# main.net
KiCad netlist of a schematic drawn in Altium Designer
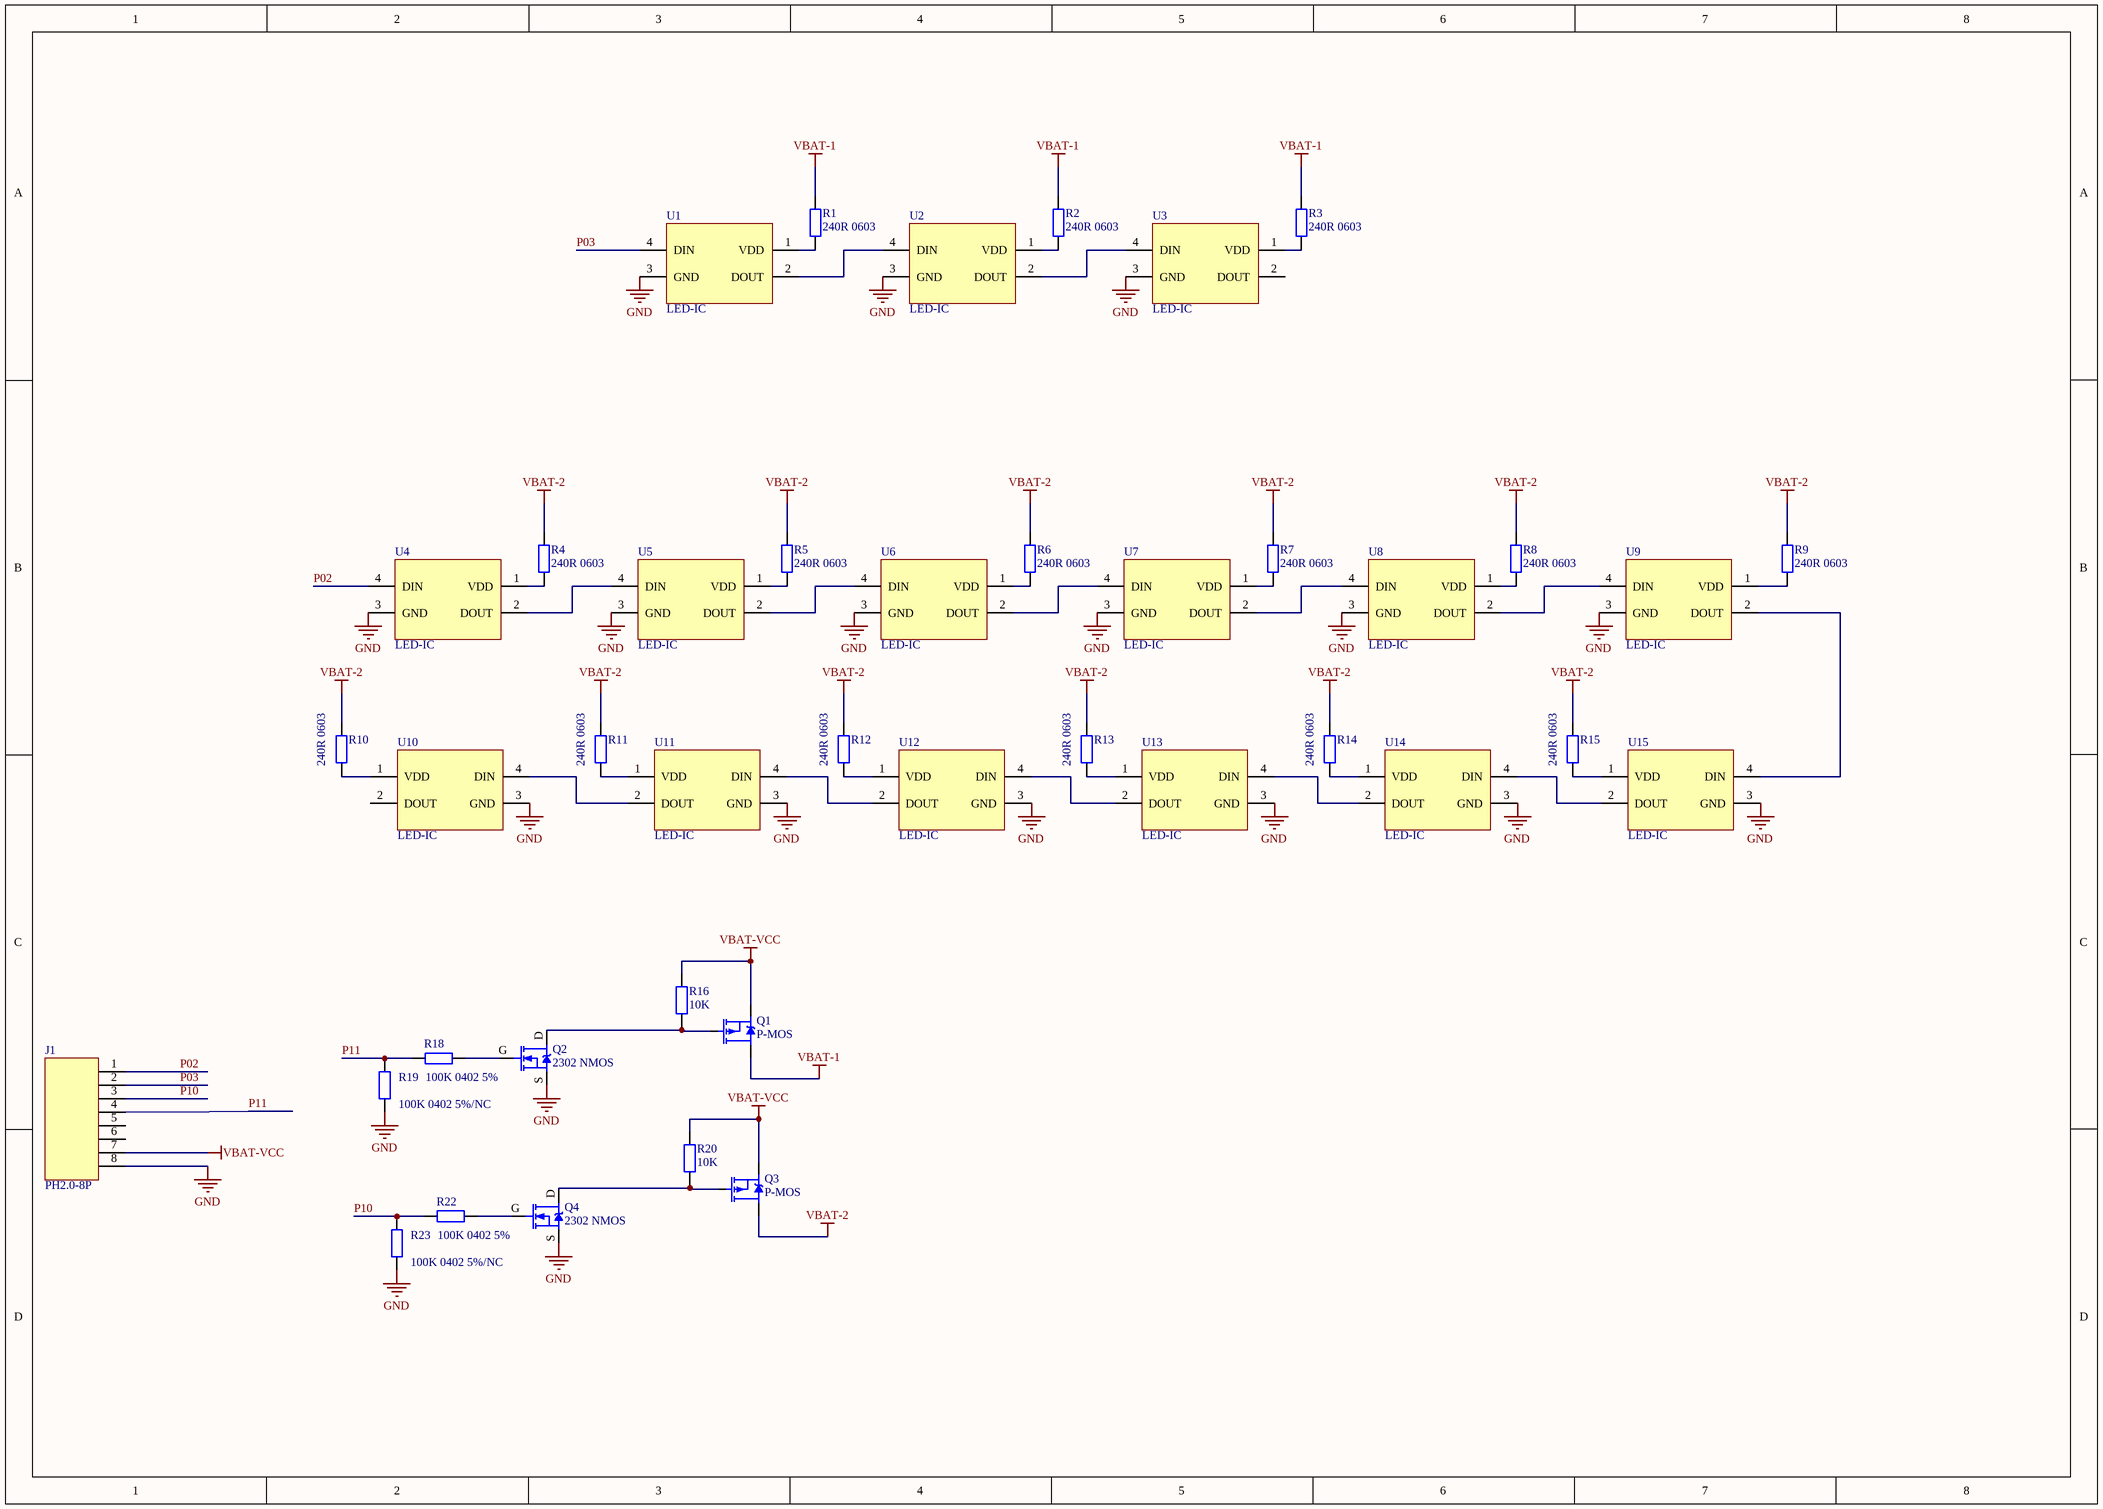
[diagram p0: main.SchDoc]

(export (version "E")
  (design (tool "Eeschema 10.0.6"))
  (components
    (comp (ref "J1") (value "PH2.0-8P") (footprint "PH2.0-8P") (libsource (lib "PH") (part "PH2.0-8P")))
    (comp (ref "Q1")
      (value "P-MOS")
      (footprint "SOT23")
      (description "P沟道场效应管")
      (libsource (lib "MOS管") (part "P-MOS"))
    )
    (comp (ref "Q2")
      (value "2302 NMOS")
      (footprint "SOT23")
      (description "N沟道场效应管")
      (libsource (lib "MOS管") (part "N-MOS"))
    )
    (comp (ref "Q3")
      (value "P-MOS")
      (footprint "SOT23")
      (description "P沟道场效应管")
      (libsource (lib "MOS管") (part "P-MOS"))
    )
    (comp (ref "Q4")
      (value "2302 NMOS")
      (footprint "SOT23")
      (description "N沟道场效应管")
      (libsource (lib "MOS管") (part "N-MOS"))
    )
    (comp (ref "R1")
      (value "240R 0603")
      (footprint "R 0603")
      (description "贴片电阻")
      (fields (field (name "版权归属") "源创客"))
      (libsource (lib "源创客") (part "R"))
    )
    (comp (ref "R2")
      (value "240R 0603")
      (footprint "R 0603")
      (description "贴片电阻")
      (fields (field (name "版权归属") "源创客"))
      (libsource (lib "源创客") (part "R"))
    )
    (comp (ref "R3")
      (value "240R 0603")
      (footprint "R 0603")
      (description "贴片电阻")
      (fields (field (name "版权归属") "源创客"))
      (libsource (lib "源创客") (part "R"))
    )
    (comp (ref "R4")
      (value "240R 0603")
      (footprint "R 0603")
      (description "贴片电阻")
      (fields (field (name "版权归属") "源创客"))
      (libsource (lib "源创客") (part "R"))
    )
    (comp (ref "R5")
      (value "240R 0603")
      (footprint "R 0603")
      (description "贴片电阻")
      (fields (field (name "版权归属") "源创客"))
      (libsource (lib "源创客") (part "R"))
    )
    (comp (ref "R6")
      (value "240R 0603")
      (footprint "R 0603")
      (description "贴片电阻")
      (fields (field (name "版权归属") "源创客"))
      (libsource (lib "源创客") (part "R"))
    )
    (comp (ref "R7")
      (value "240R 0603")
      (footprint "R 0603")
      (description "贴片电阻")
      (fields (field (name "版权归属") "源创客"))
      (libsource (lib "源创客") (part "R"))
    )
    (comp (ref "R8")
      (value "240R 0603")
      (footprint "R 0603")
      (description "贴片电阻")
      (fields (field (name "版权归属") "源创客"))
      (libsource (lib "源创客") (part "R"))
    )
    (comp (ref "R9")
      (value "240R 0603")
      (footprint "R 0603")
      (description "贴片电阻")
      (fields (field (name "版权归属") "源创客"))
      (libsource (lib "源创客") (part "R"))
    )
    (comp (ref "R10")
      (value "240R 0603")
      (footprint "R 0603")
      (description "贴片电阻")
      (fields (field (name "版权归属") "源创客"))
      (libsource (lib "源创客") (part "R"))
    )
    (comp (ref "R11")
      (value "240R 0603")
      (footprint "R 0603")
      (description "贴片电阻")
      (fields (field (name "版权归属") "源创客"))
      (libsource (lib "源创客") (part "R"))
    )
    (comp (ref "R12")
      (value "240R 0603")
      (footprint "R 0603")
      (description "贴片电阻")
      (fields (field (name "版权归属") "源创客"))
      (libsource (lib "源创客") (part "R"))
    )
    (comp (ref "R13")
      (value "240R 0603")
      (footprint "R 0603")
      (description "贴片电阻")
      (fields (field (name "版权归属") "源创客"))
      (libsource (lib "源创客") (part "R"))
    )
    (comp (ref "R14")
      (value "240R 0603")
      (footprint "R 0603")
      (description "贴片电阻")
      (fields (field (name "版权归属") "源创客"))
      (libsource (lib "源创客") (part "R"))
    )
    (comp (ref "R15")
      (value "240R 0603")
      (footprint "R 0603")
      (description "贴片电阻")
      (fields (field (name "版权归属") "源创客"))
      (libsource (lib "源创客") (part "R"))
    )
    (comp (ref "R16")
      (value "10K")
      (footprint "R 0603")
      (description "贴片电阻")
      (fields (field (name "版权归属") "源创客"))
      (libsource (lib "源创客") (part "R"))
    )
    (comp (ref "R18")
      (value "100K 0402 5%")
      (footprint "R 0603")
      (description "贴片电阻")
      (fields (field (name "版权归属") "源创客"))
      (libsource (lib "源创客") (part "R"))
    )
    (comp (ref "R19")
      (value "100K 0402 5%/NC")
      (footprint "R 0603")
      (description "贴片电阻")
      (fields (field (name "版权归属") "源创客"))
      (libsource (lib "源创客") (part "R"))
    )
    (comp (ref "R20")
      (value "10K")
      (footprint "R 0603")
      (description "贴片电阻")
      (fields (field (name "版权归属") "源创客"))
      (libsource (lib "源创客") (part "R"))
    )
    (comp (ref "R22")
      (value "100K 0402 5%")
      (footprint "R 0603")
      (description "贴片电阻")
      (fields (field (name "版权归属") "源创客"))
      (libsource (lib "源创客") (part "R"))
    )
    (comp (ref "R23")
      (value "100K 0402 5%/NC")
      (footprint "R 0603")
      (description "贴片电阻")
      (fields (field (name "版权归属") "源创客"))
      (libsource (lib "源创客") (part "R"))
    )
    (comp (ref "U1")
      (value "LED-IC")
      (footprint "LED-SMD_4P-L5.0-W5.0-BL_TC5050RGB")
      (libsource (lib "") (part "TC5050RGB_1"))
    )
    (comp (ref "U2")
      (value "LED-IC")
      (footprint "LED-SMD_4P-L5.0-W5.0-BL_TC5050RGB")
      (libsource (lib "") (part "TC5050RGB_1"))
    )
    (comp (ref "U3")
      (value "LED-IC")
      (footprint "LED-SMD_4P-L5.0-W5.0-BL_TC5050RGB")
      (libsource (lib "") (part "TC5050RGB_1"))
    )
    (comp (ref "U4")
      (value "LED-IC")
      (footprint "LED-SMD_4P-L5.0-W5.0-BL_TC5050RGB")
      (libsource (lib "") (part "TC5050RGB_1"))
    )
    (comp (ref "U5")
      (value "LED-IC")
      (footprint "LED-SMD_4P-L5.0-W5.0-BL_TC5050RGB")
      (libsource (lib "") (part "TC5050RGB_1"))
    )
    (comp (ref "U6")
      (value "LED-IC")
      (footprint "LED-SMD_4P-L5.0-W5.0-BL_TC5050RGB")
      (libsource (lib "") (part "TC5050RGB_1"))
    )
    (comp (ref "U7")
      (value "LED-IC")
      (footprint "LED-SMD_4P-L5.0-W5.0-BL_TC5050RGB")
      (libsource (lib "") (part "TC5050RGB_1"))
    )
    (comp (ref "U8")
      (value "LED-IC")
      (footprint "LED-SMD_4P-L5.0-W5.0-BL_TC5050RGB")
      (libsource (lib "") (part "TC5050RGB_1"))
    )
    (comp (ref "U9")
      (value "LED-IC")
      (footprint "LED-SMD_4P-L5.0-W5.0-BL_TC5050RGB")
      (libsource (lib "") (part "TC5050RGB_1"))
    )
    (comp (ref "U10")
      (value "LED-IC")
      (footprint "LED-SMD_4P-L5.0-W5.0-BL_TC5050RGB")
      (libsource (lib "Schlib1") (part "TC5050RGB"))
    )
    (comp (ref "U11")
      (value "LED-IC")
      (footprint "LED-SMD_4P-L5.0-W5.0-BL_TC5050RGB")
      (libsource (lib "Schlib1") (part "TC5050RGB"))
    )
    (comp (ref "U12")
      (value "LED-IC")
      (footprint "LED-SMD_4P-L5.0-W5.0-BL_TC5050RGB")
      (libsource (lib "Schlib1") (part "TC5050RGB"))
    )
    (comp (ref "U13")
      (value "LED-IC")
      (footprint "LED-SMD_4P-L5.0-W5.0-BL_TC5050RGB")
      (libsource (lib "Schlib1") (part "TC5050RGB"))
    )
    (comp (ref "U14")
      (value "LED-IC")
      (footprint "LED-SMD_4P-L5.0-W5.0-BL_TC5050RGB")
      (libsource (lib "Schlib1") (part "TC5050RGB"))
    )
    (comp (ref "U15")
      (value "LED-IC")
      (footprint "LED-SMD_4P-L5.0-W5.0-BL_TC5050RGB")
      (libsource (lib "Schlib1") (part "TC5050RGB"))
    )
  )
  (nets
    (net (code "1") (name "/P02") (class "Default")
      (node (ref "J1") (pin "1") (pinfunction "1_1") (pintype "passive"))
      (node (ref "U4") (pin "4") (pinfunction "DIN_4") (pintype "passive"))
    )
    (net (code "2") (name "/P03") (class "Default")
      (node (ref "J1") (pin "2") (pinfunction "2_2") (pintype "passive"))
      (node (ref "U1") (pin "4") (pinfunction "DIN_4") (pintype "passive"))
    )
    (net (code "3") (name "/P10") (class "Default")
      (node (ref "J1") (pin "3") (pinfunction "3_3") (pintype "passive"))
      (node (ref "R22") (pin "1") (pinfunction "1_1") (pintype "passive"))
      (node (ref "R23") (pin "2") (pinfunction "2_2") (pintype "passive"))
    )
    (net (code "4") (name "/P11") (class "Default")
      (node (ref "J1") (pin "4") (pinfunction "4_4") (pintype "passive"))
      (node (ref "R18") (pin "1") (pinfunction "1_1") (pintype "passive"))
      (node (ref "R19") (pin "2") (pinfunction "2_2") (pintype "passive"))
    )
    (net (code "5") (name "GND") (class "Default")
      (node (ref "J1") (pin "8") (pinfunction "8_8") (pintype "passive"))
      (node (ref "Q2") (pin "S") (pinfunction "S_S") (pintype "passive"))
      (node (ref "Q4") (pin "S") (pinfunction "S_S") (pintype "passive"))
      (node (ref "R19") (pin "1") (pinfunction "1_1") (pintype "passive"))
      (node (ref "R23") (pin "1") (pinfunction "1_1") (pintype "passive"))
      (node (ref "U1") (pin "3") (pinfunction "GND_3") (pintype "passive"))
      (node (ref "U10") (pin "3") (pinfunction "GND_3") (pintype "passive"))
      (node (ref "U11") (pin "3") (pinfunction "GND_3") (pintype "passive"))
      (node (ref "U12") (pin "3") (pinfunction "GND_3") (pintype "passive"))
      (node (ref "U13") (pin "3") (pinfunction "GND_3") (pintype "passive"))
      (node (ref "U14") (pin "3") (pinfunction "GND_3") (pintype "passive"))
      (node (ref "U15") (pin "3") (pinfunction "GND_3") (pintype "passive"))
      (node (ref "U2") (pin "3") (pinfunction "GND_3") (pintype "passive"))
      (node (ref "U3") (pin "3") (pinfunction "GND_3") (pintype "passive"))
      (node (ref "U4") (pin "3") (pinfunction "GND_3") (pintype "passive"))
      (node (ref "U5") (pin "3") (pinfunction "GND_3") (pintype "passive"))
      (node (ref "U6") (pin "3") (pinfunction "GND_3") (pintype "passive"))
      (node (ref "U7") (pin "3") (pinfunction "GND_3") (pintype "passive"))
      (node (ref "U8") (pin "3") (pinfunction "GND_3") (pintype "passive"))
      (node (ref "U9") (pin "3") (pinfunction "GND_3") (pintype "passive"))
    )
    (net (code "6") (name "Net-(Q1-PadG)") (class "Default")
      (node (ref "Q1") (pin "G") (pinfunction "G_G") (pintype "passive"))
      (node (ref "Q2") (pin "D") (pinfunction "D_D") (pintype "passive"))
      (node (ref "R16") (pin "1") (pinfunction "1_1") (pintype "passive"))
    )
    (net (code "7") (name "Net-(Q2-PadG)") (class "Default")
      (node (ref "Q2") (pin "G") (pinfunction "G_G") (pintype "passive"))
      (node (ref "R18") (pin "2") (pinfunction "2_2") (pintype "passive"))
    )
    (net (code "8") (name "Net-(Q3-PadG)") (class "Default")
      (node (ref "Q3") (pin "G") (pinfunction "G_G") (pintype "passive"))
      (node (ref "Q4") (pin "D") (pinfunction "D_D") (pintype "passive"))
      (node (ref "R20") (pin "1") (pinfunction "1_1") (pintype "passive"))
    )
    (net (code "9") (name "Net-(Q4-PadG)") (class "Default")
      (node (ref "Q4") (pin "G") (pinfunction "G_G") (pintype "passive"))
      (node (ref "R22") (pin "2") (pinfunction "2_2") (pintype "passive"))
    )
    (net (code "10") (name "Net-(U1-DOUT)") (class "Default")
      (node (ref "U1") (pin "2") (pinfunction "DOUT_2") (pintype "passive"))
      (node (ref "U2") (pin "4") (pinfunction "DIN_4") (pintype "passive"))
    )
    (net (code "11") (name "Net-(U1-VDD)") (class "Default")
      (node (ref "R1") (pin "1") (pinfunction "1_1") (pintype "passive"))
      (node (ref "U1") (pin "1") (pinfunction "VDD_1") (pintype "passive"))
    )
    (net (code "12") (name "Net-(U2-DOUT)") (class "Default")
      (node (ref "U2") (pin "2") (pinfunction "DOUT_2") (pintype "passive"))
      (node (ref "U3") (pin "4") (pinfunction "DIN_4") (pintype "passive"))
    )
    (net (code "13") (name "Net-(U2-VDD)") (class "Default")
      (node (ref "R2") (pin "1") (pinfunction "1_1") (pintype "passive"))
      (node (ref "U2") (pin "1") (pinfunction "VDD_1") (pintype "passive"))
    )
    (net (code "14") (name "Net-(U3-VDD)") (class "Default")
      (node (ref "R3") (pin "1") (pinfunction "1_1") (pintype "passive"))
      (node (ref "U3") (pin "1") (pinfunction "VDD_1") (pintype "passive"))
    )
    (net (code "15") (name "Net-(U4-DOUT)") (class "Default")
      (node (ref "U4") (pin "2") (pinfunction "DOUT_2") (pintype "passive"))
      (node (ref "U5") (pin "4") (pinfunction "DIN_4") (pintype "passive"))
    )
    (net (code "16") (name "Net-(U4-VDD)") (class "Default")
      (node (ref "R4") (pin "1") (pinfunction "1_1") (pintype "passive"))
      (node (ref "U4") (pin "1") (pinfunction "VDD_1") (pintype "passive"))
    )
    (net (code "17") (name "Net-(U5-DOUT)") (class "Default")
      (node (ref "U5") (pin "2") (pinfunction "DOUT_2") (pintype "passive"))
      (node (ref "U6") (pin "4") (pinfunction "DIN_4") (pintype "passive"))
    )
    (net (code "18") (name "Net-(U5-VDD)") (class "Default")
      (node (ref "R5") (pin "1") (pinfunction "1_1") (pintype "passive"))
      (node (ref "U5") (pin "1") (pinfunction "VDD_1") (pintype "passive"))
    )
    (net (code "19") (name "Net-(U6-DOUT)") (class "Default")
      (node (ref "U6") (pin "2") (pinfunction "DOUT_2") (pintype "passive"))
      (node (ref "U7") (pin "4") (pinfunction "DIN_4") (pintype "passive"))
    )
    (net (code "20") (name "Net-(U6-VDD)") (class "Default")
      (node (ref "R6") (pin "1") (pinfunction "1_1") (pintype "passive"))
      (node (ref "U6") (pin "1") (pinfunction "VDD_1") (pintype "passive"))
    )
    (net (code "21") (name "Net-(U7-DOUT)") (class "Default")
      (node (ref "U7") (pin "2") (pinfunction "DOUT_2") (pintype "passive"))
      (node (ref "U8") (pin "4") (pinfunction "DIN_4") (pintype "passive"))
    )
    (net (code "22") (name "Net-(U7-VDD)") (class "Default")
      (node (ref "R7") (pin "1") (pinfunction "1_1") (pintype "passive"))
      (node (ref "U7") (pin "1") (pinfunction "VDD_1") (pintype "passive"))
    )
    (net (code "23") (name "Net-(U8-DOUT)") (class "Default")
      (node (ref "U8") (pin "2") (pinfunction "DOUT_2") (pintype "passive"))
      (node (ref "U9") (pin "4") (pinfunction "DIN_4") (pintype "passive"))
    )
    (net (code "24") (name "Net-(U8-VDD)") (class "Default")
      (node (ref "R8") (pin "1") (pinfunction "1_1") (pintype "passive"))
      (node (ref "U8") (pin "1") (pinfunction "VDD_1") (pintype "passive"))
    )
    (net (code "25") (name "Net-(U9-VDD)") (class "Default")
      (node (ref "R9") (pin "1") (pinfunction "1_1") (pintype "passive"))
      (node (ref "U9") (pin "1") (pinfunction "VDD_1") (pintype "passive"))
    )
    (net (code "26") (name "Net-(U10-DIN)") (class "Default")
      (node (ref "U10") (pin "4") (pinfunction "DIN_4") (pintype "passive"))
      (node (ref "U11") (pin "2") (pinfunction "DOUT_2") (pintype "passive"))
    )
    (net (code "27") (name "Net-(U10-VDD)") (class "Default")
      (node (ref "R10") (pin "1") (pinfunction "1_1") (pintype "passive"))
      (node (ref "U10") (pin "1") (pinfunction "VDD_1") (pintype "passive"))
    )
    (net (code "28") (name "Net-(U11-DIN)") (class "Default")
      (node (ref "U11") (pin "4") (pinfunction "DIN_4") (pintype "passive"))
      (node (ref "U12") (pin "2") (pinfunction "DOUT_2") (pintype "passive"))
    )
    (net (code "29") (name "Net-(U11-VDD)") (class "Default")
      (node (ref "R11") (pin "1") (pinfunction "1_1") (pintype "passive"))
      (node (ref "U11") (pin "1") (pinfunction "VDD_1") (pintype "passive"))
    )
    (net (code "30") (name "Net-(U12-DIN)") (class "Default")
      (node (ref "U12") (pin "4") (pinfunction "DIN_4") (pintype "passive"))
      (node (ref "U13") (pin "2") (pinfunction "DOUT_2") (pintype "passive"))
    )
    (net (code "31") (name "Net-(U12-VDD)") (class "Default")
      (node (ref "R12") (pin "1") (pinfunction "1_1") (pintype "passive"))
      (node (ref "U12") (pin "1") (pinfunction "VDD_1") (pintype "passive"))
    )
    (net (code "32") (name "Net-(U13-DIN)") (class "Default")
      (node (ref "U13") (pin "4") (pinfunction "DIN_4") (pintype "passive"))
      (node (ref "U14") (pin "2") (pinfunction "DOUT_2") (pintype "passive"))
    )
    (net (code "33") (name "Net-(U13-VDD)") (class "Default")
      (node (ref "R13") (pin "1") (pinfunction "1_1") (pintype "passive"))
      (node (ref "U13") (pin "1") (pinfunction "VDD_1") (pintype "passive"))
    )
    (net (code "34") (name "Net-(U14-DIN)") (class "Default")
      (node (ref "U14") (pin "4") (pinfunction "DIN_4") (pintype "passive"))
      (node (ref "U15") (pin "2") (pinfunction "DOUT_2") (pintype "passive"))
    )
    (net (code "35") (name "Net-(U14-VDD)") (class "Default")
      (node (ref "R14") (pin "1") (pinfunction "1_1") (pintype "passive"))
      (node (ref "U14") (pin "1") (pinfunction "VDD_1") (pintype "passive"))
    )
    (net (code "36") (name "Net-(U15-DIN)") (class "Default")
      (node (ref "U15") (pin "4") (pinfunction "DIN_4") (pintype "passive"))
      (node (ref "U9") (pin "2") (pinfunction "DOUT_2") (pintype "passive"))
    )
    (net (code "37") (name "Net-(U15-VDD)") (class "Default")
      (node (ref "R15") (pin "1") (pinfunction "1_1") (pintype "passive"))
      (node (ref "U15") (pin "1") (pinfunction "VDD_1") (pintype "passive"))
    )
    (net (code "38") (name "VBAT-1") (class "Default")
      (node (ref "Q1") (pin "D") (pinfunction "D_D") (pintype "passive"))
      (node (ref "R1") (pin "2") (pinfunction "2_2") (pintype "passive"))
      (node (ref "R2") (pin "2") (pinfunction "2_2") (pintype "passive"))
      (node (ref "R3") (pin "2") (pinfunction "2_2") (pintype "passive"))
    )
    (net (code "39") (name "VBAT-2") (class "Default")
      (node (ref "Q3") (pin "D") (pinfunction "D_D") (pintype "passive"))
      (node (ref "R10") (pin "2") (pinfunction "2_2") (pintype "passive"))
      (node (ref "R11") (pin "2") (pinfunction "2_2") (pintype "passive"))
      (node (ref "R12") (pin "2") (pinfunction "2_2") (pintype "passive"))
      (node (ref "R13") (pin "2") (pinfunction "2_2") (pintype "passive"))
      (node (ref "R14") (pin "2") (pinfunction "2_2") (pintype "passive"))
      (node (ref "R15") (pin "2") (pinfunction "2_2") (pintype "passive"))
      (node (ref "R4") (pin "2") (pinfunction "2_2") (pintype "passive"))
      (node (ref "R5") (pin "2") (pinfunction "2_2") (pintype "passive"))
      (node (ref "R6") (pin "2") (pinfunction "2_2") (pintype "passive"))
      (node (ref "R7") (pin "2") (pinfunction "2_2") (pintype "passive"))
      (node (ref "R8") (pin "2") (pinfunction "2_2") (pintype "passive"))
      (node (ref "R9") (pin "2") (pinfunction "2_2") (pintype "passive"))
    )
    (net (code "40") (name "VBAT-VCC") (class "Default")
      (node (ref "J1") (pin "7") (pinfunction "7_7") (pintype "passive"))
      (node (ref "Q1") (pin "S") (pinfunction "S_S") (pintype "passive"))
      (node (ref "Q3") (pin "S") (pinfunction "S_S") (pintype "passive"))
      (node (ref "R16") (pin "2") (pinfunction "2_2") (pintype "passive"))
      (node (ref "R20") (pin "2") (pinfunction "2_2") (pintype "passive"))
    )
    (net (code "41") (name "unconnected-(J1-Pad5)") (class "Default")
      (node (ref "J1") (pin "5") (pinfunction "5_5") (pintype "passive"))
    )
    (net (code "42") (name "unconnected-(J1-Pad6)") (class "Default")
      (node (ref "J1") (pin "6") (pinfunction "6_6") (pintype "passive"))
    )
    (net (code "43") (name "unconnected-(U3-DOUT-Pad2)") (class "Default")
      (node (ref "U3") (pin "2") (pinfunction "DOUT_2") (pintype "passive"))
    )
    (net (code "44") (name "unconnected-(U10-DOUT-Pad2)") (class "Default")
      (node (ref "U10") (pin "2") (pinfunction "DOUT_2") (pintype "passive"))
    )
  )
)
